# main_board.net
KiCad netlist of a schematic drawn in EAGLE
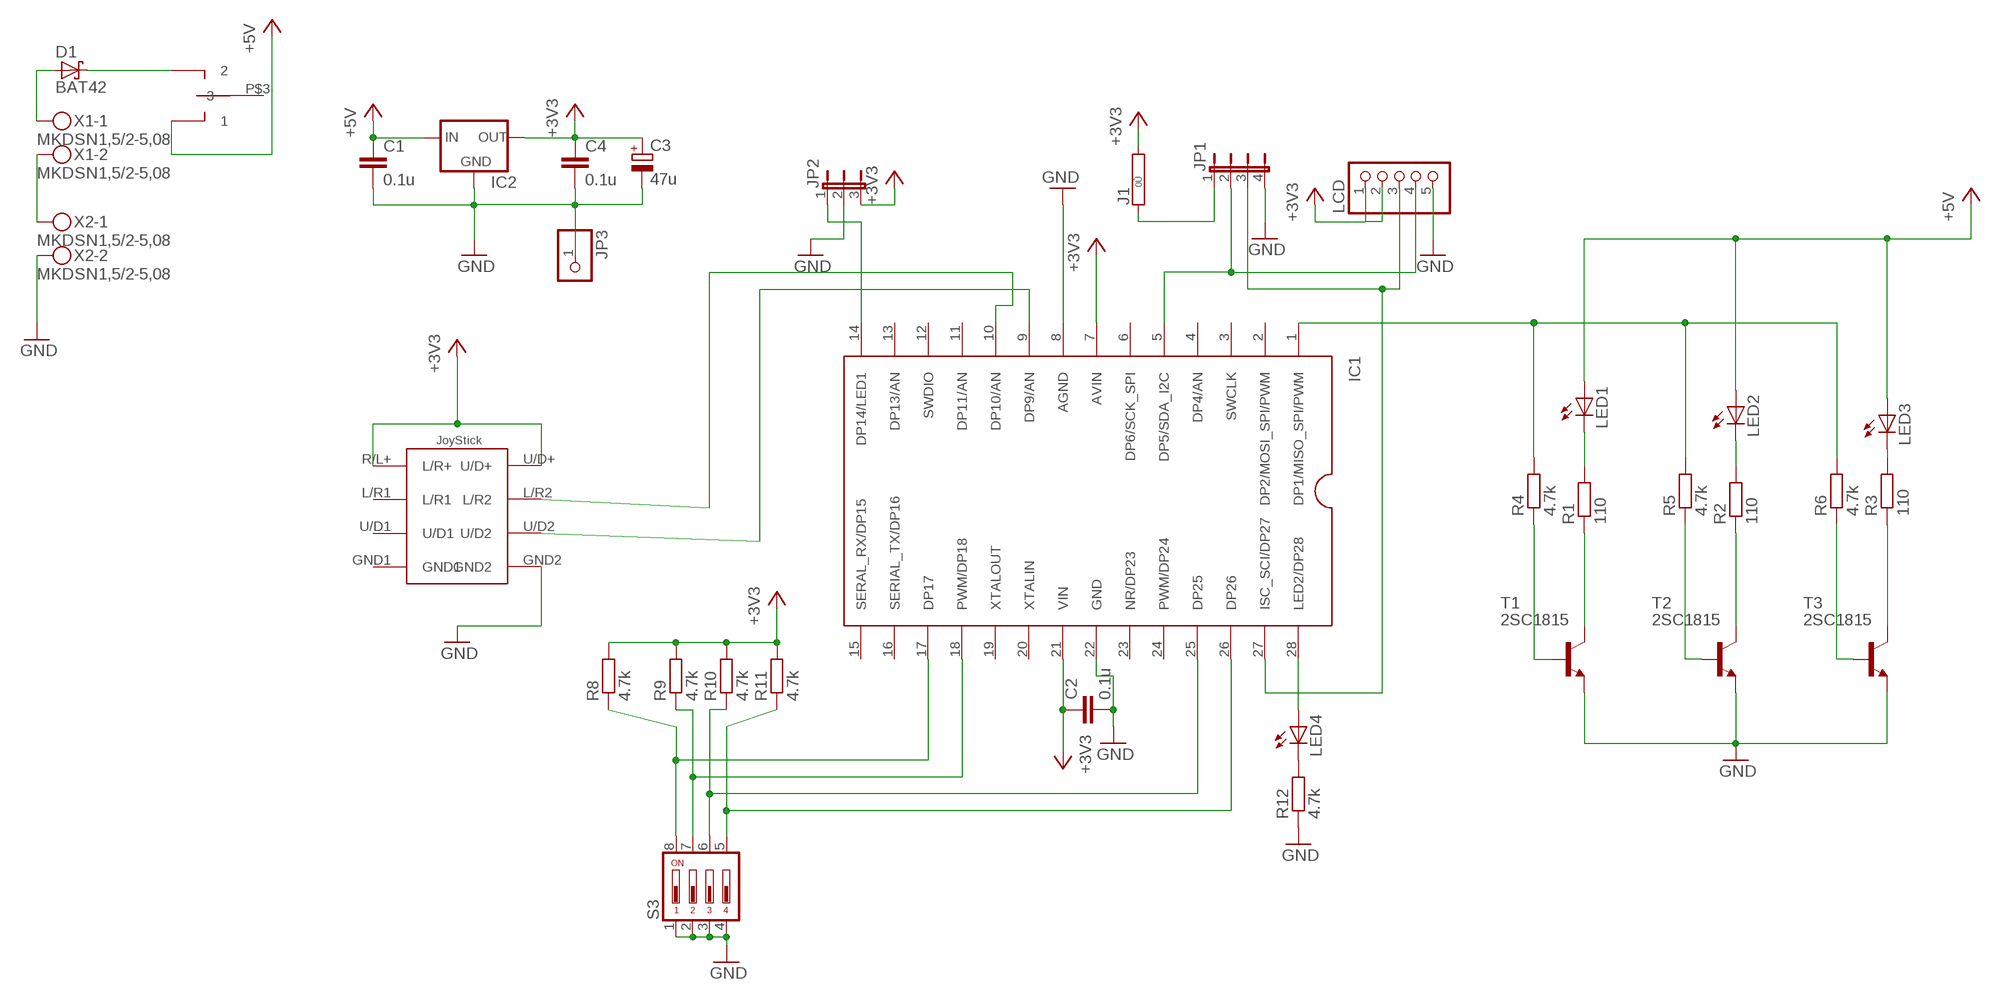
[diagram p0: schematic, sheet 1]

(export (version "E")
  (design (tool "Eeschema 10.0.6"))
  (components
    (comp (ref "C1")
      (value "0.1u")
      (footprint "eagle-import:C025-024X044")
      (libsource (lib "eagle-import") (part "C-EU025-024X044"))
    )
    (comp (ref "C2")
      (value "0.1u")
      (footprint "eagle-import:C025-024X044")
      (libsource (lib "eagle-import") (part "C-EU025-024X044"))
    )
    (comp (ref "C3")
      (value "47u")
      (footprint "eagle-import:E2,5-5")
      (libsource (lib "eagle-import") (part "CPOL-EUE2.5-5"))
    )
    (comp (ref "C4")
      (value "0.1u")
      (footprint "eagle-import:C025-024X044")
      (libsource (lib "eagle-import") (part "C-EU025-024X044"))
    )
    (comp (ref "D1")
      (value "BAT42")
      (footprint "eagle-import:DO35-10")
      (libsource (lib "eagle-import") (part "BAT42"))
    )
    (comp (ref "IC1")
      (value "LPC1114FN28")
      (footprint "eagle-import:DIP28")
      (libsource (lib "eagle-import") (part "LPC1114FN28"))
    )
    (comp (ref "IC2")
      (value "78XXL")
      (footprint "eagle-import:78XXL")
      (libsource (lib "eagle-import") (part "78XXL"))
    )
    (comp (ref "J1")
      (value "0R")
      (footprint "eagle-import:0R_10")
      (libsource (lib "eagle-import") (part "0R"))
    )
    (comp (ref "JP1")
      (value "JP4E")
      (footprint "eagle-import:JP4")
      (libsource (lib "eagle-import") (part "JP4E"))
    )
    (comp (ref "JP2")
      (value "JP2E")
      (footprint "eagle-import:JP2")
      (libsource (lib "eagle-import") (part "JP2E"))
    )
    (comp (ref "JP3")
      (value "PINHD-1X1")
      (footprint "eagle-import:1X01")
      (libsource (lib "eagle-import") (part "PINHD-1X1"))
    )
    (comp (ref "LCD")
      (value "PINHD-1X5")
      (footprint "eagle-import:1X05")
      (libsource (lib "eagle-import") (part "PINHD-1X5"))
    )
    (comp (ref "LED1")
      (value "LED5MM")
      (footprint "eagle-import:LED5MM")
      (libsource (lib "eagle-import") (part "LED5MM"))
    )
    (comp (ref "LED2")
      (value "LED5MM")
      (footprint "eagle-import:LED5MM")
      (libsource (lib "eagle-import") (part "LED5MM"))
    )
    (comp (ref "LED3")
      (value "LED5MM")
      (footprint "eagle-import:LED5MM")
      (libsource (lib "eagle-import") (part "LED5MM"))
    )
    (comp (ref "LED4")
      (value "LED3MM")
      (footprint "eagle-import:LED3MM")
      (libsource (lib "eagle-import") (part "LED3MM"))
    )
    (comp (ref "R1")
      (value "110")
      (footprint "eagle-import:0207_10")
      (libsource (lib "eagle-import") (part "R-EU_0207/10"))
    )
    (comp (ref "R2")
      (value "110")
      (footprint "eagle-import:0207_10")
      (libsource (lib "eagle-import") (part "R-EU_0207/10"))
    )
    (comp (ref "R3")
      (value "110")
      (footprint "eagle-import:0207_10")
      (libsource (lib "eagle-import") (part "R-EU_0207/10"))
    )
    (comp (ref "R4")
      (value "4.7k")
      (footprint "eagle-import:0204_7")
      (libsource (lib "eagle-import") (part "R-EU_0204/7"))
    )
    (comp (ref "R5")
      (value "4.7k")
      (footprint "eagle-import:0204_7")
      (libsource (lib "eagle-import") (part "R-EU_0204/7"))
    )
    (comp (ref "R6")
      (value "4.7k")
      (footprint "eagle-import:0204_7")
      (libsource (lib "eagle-import") (part "R-EU_0204/7"))
    )
    (comp (ref "R8")
      (value "4.7k")
      (footprint "eagle-import:0204_7")
      (libsource (lib "eagle-import") (part "R-EU_0204/7"))
    )
    (comp (ref "R9")
      (value "4.7k")
      (footprint "eagle-import:0204_7")
      (libsource (lib "eagle-import") (part "R-EU_0204/7"))
    )
    (comp (ref "R10")
      (value "4.7k")
      (footprint "eagle-import:0204_7")
      (libsource (lib "eagle-import") (part "R-EU_0204/7"))
    )
    (comp (ref "R11")
      (value "4.7k")
      (footprint "eagle-import:0204_7")
      (libsource (lib "eagle-import") (part "R-EU_0204/7"))
    )
    (comp (ref "R12")
      (value "4.7k")
      (footprint "eagle-import:0204_7")
      (libsource (lib "eagle-import") (part "R-EU_0204/7"))
    )
    (comp (ref "S3")
      (value "DIP04YL")
      (footprint "eagle-import:DIP04YL")
      (libsource (lib "eagle-import") (part "DIP04YL"))
    )
    (comp (ref "T1")
      (value "2SC1815")
      (footprint "eagle-import:TO92-ECB")
      (libsource (lib "eagle-import") (part "2SC1815"))
    )
    (comp (ref "T2")
      (value "2SC1815")
      (footprint "eagle-import:TO92-ECB")
      (libsource (lib "eagle-import") (part "2SC1815"))
    )
    (comp (ref "T3")
      (value "2SC1815")
      (footprint "eagle-import:TO92-ECB")
      (libsource (lib "eagle-import") (part "2SC1815"))
    )
    (comp (ref "U$1")
      (value "ANALOGJOYSTICK")
      (footprint "eagle-import:ANLOGJOYSTICK")
      (libsource (lib "eagle-import") (part "ANALOGJOYSTICK"))
    )
    (comp (ref "U$2")
      (value "TOGGLE-B-12JV")
      (footprint "eagle-import:TOGGLE-B-12JV")
      (libsource (lib "eagle-import") (part "TOGGLE-B-12JV"))
    )
    (comp (ref "X1")
      (value "MKDSN1,5/2-5,08")
      (footprint "eagle-import:MKDSN1,5_2-5,08")
      (libsource (lib "eagle-import") (part "MKDSN1,5/2-5,08"))
    )
    (comp (ref "X2")
      (value "MKDSN1,5/2-5,08")
      (footprint "eagle-import:MKDSN1,5_2-5,08")
      (libsource (lib "eagle-import") (part "MKDSN1,5/2-5,08"))
    )
  )
  (nets
    (net (code "1") (name "+3V3") (class "Default")
      (node (ref "C2") (pin "1") (pinfunction "1_1") (pintype "passive"))
      (node (ref "C3") (pin "+") (pinfunction "+_+") (pintype "passive"))
      (node (ref "C4") (pin "1") (pinfunction "1_1") (pintype "passive"))
      (node (ref "IC1") (pin "21") (pinfunction "VIN_21") (pintype "power_in"))
      (node (ref "IC1") (pin "7") (pinfunction "AVIN_7") (pintype "power_in"))
      (node (ref "IC2") (pin "OUT") (pinfunction "OUT_OUT") (pintype "passive"))
      (node (ref "J1") (pin "2") (pinfunction "2_2") (pintype "passive"))
      (node (ref "JP2") (pin "3") (pinfunction "3_3") (pintype "passive"))
      (node (ref "LCD") (pin "1") (pinfunction "1_1") (pintype "passive"))
      (node (ref "LCD") (pin "2") (pinfunction "2_2") (pintype "passive"))
      (node (ref "R10") (pin "2") (pinfunction "2_2") (pintype "passive"))
      (node (ref "R11") (pin "2") (pinfunction "2_2") (pintype "passive"))
      (node (ref "R8") (pin "2") (pinfunction "2_2") (pintype "passive"))
      (node (ref "R9") (pin "2") (pinfunction "2_2") (pintype "passive"))
      (node (ref "U$1") (pin "R/L+") (pinfunction "L/R+_R/L+") (pintype "bidirectional"))
      (node (ref "U$1") (pin "U/D+") (pinfunction "U/D+_U/D+") (pintype "bidirectional"))
    )
    (net (code "2") (name "+5V") (class "Default")
      (node (ref "C1") (pin "1") (pinfunction "1_1") (pintype "passive"))
      (node (ref "IC2") (pin "IN") (pinfunction "IN_IN") (pintype "input"))
      (node (ref "LED1") (pin "A") (pinfunction "A_A") (pintype "passive"))
      (node (ref "LED2") (pin "A") (pinfunction "A_A") (pintype "passive"))
      (node (ref "LED3") (pin "A") (pinfunction "A_A") (pintype "passive"))
      (node (ref "U$2") (pin "P$1") (pinfunction "1_P$1") (pintype "bidirectional"))
    )
    (net (code "3") (name "GND") (class "Default")
      (node (ref "C1") (pin "2") (pinfunction "2_2") (pintype "passive"))
      (node (ref "C2") (pin "2") (pinfunction "2_2") (pintype "passive"))
      (node (ref "C3") (pin "-") (pinfunction "-_-") (pintype "passive"))
      (node (ref "C4") (pin "2") (pinfunction "2_2") (pintype "passive"))
      (node (ref "IC1") (pin "22") (pinfunction "GND_22") (pintype "power_in"))
      (node (ref "IC1") (pin "8") (pinfunction "AGND_8") (pintype "power_in"))
      (node (ref "IC2") (pin "GND") (pinfunction "GND_GND") (pintype "input"))
      (node (ref "JP1") (pin "4") (pinfunction "4_4") (pintype "passive"))
      (node (ref "JP2") (pin "2") (pinfunction "2_2") (pintype "passive"))
      (node (ref "JP3") (pin "1") (pinfunction "1_1") (pintype "passive"))
      (node (ref "LCD") (pin "5") (pinfunction "5_5") (pintype "passive"))
      (node (ref "R12") (pin "1") (pinfunction "1_1") (pintype "passive"))
      (node (ref "S3") (pin "1") (pinfunction "1_1") (pintype "passive"))
      (node (ref "S3") (pin "2") (pinfunction "2_2") (pintype "passive"))
      (node (ref "S3") (pin "3") (pinfunction "3_3") (pintype "passive"))
      (node (ref "S3") (pin "4") (pinfunction "4_4") (pintype "passive"))
      (node (ref "T1") (pin "E") (pinfunction "E_E") (pintype "passive"))
      (node (ref "T2") (pin "E") (pinfunction "E_E") (pintype "passive"))
      (node (ref "T3") (pin "E") (pinfunction "E_E") (pintype "passive"))
      (node (ref "U$1") (pin "GND2") (pinfunction "GND2_GND2") (pintype "bidirectional"))
      (node (ref "X2") (pin "2") (pinfunction "KL_2") (pintype "passive"))
    )
    (net (code "4") (name "Net-(IC1-DP1{slash}MISO_SPI{slash}PWM)") (class "Default")
      (node (ref "IC1") (pin "1") (pinfunction "DP1/MISO_SPI/PWM_1") (pintype "bidirectional"))
      (node (ref "R4") (pin "2") (pinfunction "2_2") (pintype "passive"))
      (node (ref "R5") (pin "2") (pinfunction "2_2") (pintype "passive"))
      (node (ref "R6") (pin "2") (pinfunction "2_2") (pintype "passive"))
    )
    (net (code "5") (name "Net-(IC1-DP5{slash}SDA_I2C)") (class "Default")
      (node (ref "IC1") (pin "5") (pinfunction "DP5/SDA_I2C_5") (pintype "bidirectional"))
      (node (ref "JP1") (pin "2") (pinfunction "2_2") (pintype "passive"))
      (node (ref "LCD") (pin "4") (pinfunction "4_4") (pintype "passive"))
    )
    (net (code "6") (name "Net-(IC1-DP9{slash}AN)") (class "Default")
      (node (ref "IC1") (pin "9") (pinfunction "DP9/AN_9") (pintype "bidirectional"))
      (node (ref "U$1") (pin "U/D2") (pinfunction "U/D2_U/D2") (pintype "bidirectional"))
    )
    (net (code "7") (name "Net-(IC1-DP10{slash}AN)") (class "Default")
      (node (ref "IC1") (pin "10") (pinfunction "DP10/AN_10") (pintype "bidirectional"))
      (node (ref "U$1") (pin "L/R2") (pinfunction "L/R2_L/R2") (pintype "bidirectional"))
    )
    (net (code "8") (name "Net-(IC1-DP14{slash}LED1)") (class "Default")
      (node (ref "IC1") (pin "14") (pinfunction "DP14/LED1_14") (pintype "bidirectional"))
      (node (ref "JP2") (pin "1") (pinfunction "1_1") (pintype "passive"))
    )
    (net (code "9") (name "Net-(IC1-DP17)") (class "Default")
      (node (ref "IC1") (pin "17") (pinfunction "DP17_17") (pintype "bidirectional"))
      (node (ref "R8") (pin "1") (pinfunction "1_1") (pintype "passive"))
      (node (ref "S3") (pin "8") (pinfunction "8_8") (pintype "passive"))
    )
    (net (code "10") (name "Net-(IC1-DP25)") (class "Default")
      (node (ref "IC1") (pin "25") (pinfunction "DP25_25") (pintype "bidirectional"))
      (node (ref "R10") (pin "1") (pinfunction "1_1") (pintype "passive"))
      (node (ref "S3") (pin "6") (pinfunction "6_6") (pintype "passive"))
    )
    (net (code "11") (name "Net-(IC1-DP26)") (class "Default")
      (node (ref "IC1") (pin "26") (pinfunction "DP26_26") (pintype "bidirectional"))
      (node (ref "R11") (pin "1") (pinfunction "1_1") (pintype "passive"))
      (node (ref "S3") (pin "5") (pinfunction "5_5") (pintype "passive"))
    )
    (net (code "12") (name "Net-(IC1-ISC_SCI{slash}DP27)") (class "Default")
      (node (ref "IC1") (pin "27") (pinfunction "ISC_SCI/DP27_27") (pintype "bidirectional"))
      (node (ref "JP1") (pin "3") (pinfunction "3_3") (pintype "passive"))
      (node (ref "LCD") (pin "3") (pinfunction "3_3") (pintype "passive"))
    )
    (net (code "13") (name "Net-(IC1-LED2{slash}DP28)") (class "Default")
      (node (ref "IC1") (pin "28") (pinfunction "LED2/DP28_28") (pintype "bidirectional"))
      (node (ref "LED4") (pin "A") (pinfunction "A_A") (pintype "passive"))
    )
    (net (code "14") (name "Net-(IC1-PWM{slash}DP18)") (class "Default")
      (node (ref "IC1") (pin "18") (pinfunction "PWM/DP18_18") (pintype "bidirectional"))
      (node (ref "R9") (pin "1") (pinfunction "1_1") (pintype "passive"))
      (node (ref "S3") (pin "7") (pinfunction "7_7") (pintype "passive"))
    )
    (net (code "15") (name "Net-(J1-Pad1)") (class "Default")
      (node (ref "J1") (pin "1") (pinfunction "1_1") (pintype "passive"))
      (node (ref "JP1") (pin "1") (pinfunction "1_1") (pintype "passive"))
    )
    (net (code "16") (name "Net-(LED1-C)") (class "Default")
      (node (ref "LED1") (pin "K") (pinfunction "C_K") (pintype "passive"))
      (node (ref "R1") (pin "2") (pinfunction "2_2") (pintype "passive"))
    )
    (net (code "17") (name "Net-(LED2-C)") (class "Default")
      (node (ref "LED2") (pin "K") (pinfunction "C_K") (pintype "passive"))
      (node (ref "R2") (pin "2") (pinfunction "2_2") (pintype "passive"))
    )
    (net (code "18") (name "Net-(LED3-C)") (class "Default")
      (node (ref "LED3") (pin "K") (pinfunction "C_K") (pintype "passive"))
      (node (ref "R3") (pin "2") (pinfunction "2_2") (pintype "passive"))
    )
    (net (code "19") (name "Net-(LED4-C)") (class "Default")
      (node (ref "LED4") (pin "K") (pinfunction "C_K") (pintype "passive"))
      (node (ref "R12") (pin "2") (pinfunction "2_2") (pintype "passive"))
    )
    (net (code "20") (name "Net-(R1-Pad1)") (class "Default")
      (node (ref "R1") (pin "1") (pinfunction "1_1") (pintype "passive"))
      (node (ref "T1") (pin "C") (pinfunction "C_C") (pintype "passive"))
    )
    (net (code "21") (name "Net-(R2-Pad1)") (class "Default")
      (node (ref "R2") (pin "1") (pinfunction "1_1") (pintype "passive"))
      (node (ref "T2") (pin "C") (pinfunction "C_C") (pintype "passive"))
    )
    (net (code "22") (name "Net-(R3-Pad1)") (class "Default")
      (node (ref "R3") (pin "1") (pinfunction "1_1") (pintype "passive"))
      (node (ref "T3") (pin "C") (pinfunction "C_C") (pintype "passive"))
    )
    (net (code "23") (name "Net-(R4-Pad1)") (class "Default")
      (node (ref "R4") (pin "1") (pinfunction "1_1") (pintype "passive"))
      (node (ref "T1") (pin "B") (pinfunction "B_B") (pintype "passive"))
    )
    (net (code "24") (name "Net-(R5-Pad1)") (class "Default")
      (node (ref "R5") (pin "1") (pinfunction "1_1") (pintype "passive"))
      (node (ref "T2") (pin "B") (pinfunction "B_B") (pintype "passive"))
    )
    (net (code "25") (name "Net-(R6-Pad1)") (class "Default")
      (node (ref "R6") (pin "1") (pinfunction "1_1") (pintype "passive"))
      (node (ref "T3") (pin "B") (pinfunction "B_B") (pintype "passive"))
    )
    (net (code "26") (name "Net-(U$2-2)") (class "Default")
      (node (ref "D1") (pin "C") (pinfunction "C_C") (pintype "passive"))
      (node (ref "U$2") (pin "P$2") (pinfunction "2_P$2") (pintype "bidirectional"))
    )
    (net (code "27") (name "Net-(X1A-KL)") (class "Default")
      (node (ref "D1") (pin "A") (pinfunction "A_A") (pintype "passive"))
      (node (ref "X1") (pin "1") (pinfunction "KL_1") (pintype "passive"))
    )
    (net (code "28") (name "Net-(X1B-KL)") (class "Default")
      (node (ref "X1") (pin "2") (pinfunction "KL_2") (pintype "passive"))
      (node (ref "X2") (pin "1") (pinfunction "KL_1") (pintype "passive"))
    )
    (net (code "29") (name "unconnected-(IC1-DP2{slash}MOSI_SPI{slash}PWM-Pad2)") (class "Default")
      (node (ref "IC1") (pin "2") (pinfunction "DP2/MOSI_SPI/PWM_2") (pintype "bidirectional"))
    )
    (net (code "30") (name "unconnected-(IC1-DP4{slash}AN-Pad4)") (class "Default")
      (node (ref "IC1") (pin "4") (pinfunction "DP4/AN_4") (pintype "bidirectional"))
    )
    (net (code "31") (name "unconnected-(IC1-DP6{slash}SCK_SPI-Pad6)") (class "Default")
      (node (ref "IC1") (pin "6") (pinfunction "DP6/SCK_SPI_6") (pintype "bidirectional"))
    )
    (net (code "32") (name "unconnected-(IC1-DP11{slash}AN-Pad11)") (class "Default")
      (node (ref "IC1") (pin "11") (pinfunction "DP11/AN_11") (pintype "bidirectional"))
    )
    (net (code "33") (name "unconnected-(IC1-DP13{slash}AN-Pad13)") (class "Default")
      (node (ref "IC1") (pin "13") (pinfunction "DP13/AN_13") (pintype "bidirectional"))
    )
    (net (code "34") (name "unconnected-(IC1-NR{slash}DP23-Pad23)") (class "Default")
      (node (ref "IC1") (pin "23") (pinfunction "NR/DP23_23") (pintype "bidirectional"))
    )
    (net (code "35") (name "unconnected-(IC1-PWM{slash}DP24-Pad24)") (class "Default")
      (node (ref "IC1") (pin "24") (pinfunction "PWM/DP24_24") (pintype "bidirectional"))
    )
    (net (code "36") (name "unconnected-(IC1-SERAL_RX{slash}DP15-Pad15)") (class "Default")
      (node (ref "IC1") (pin "15") (pinfunction "SERAL_RX/DP15_15") (pintype "bidirectional"))
    )
    (net (code "37") (name "unconnected-(IC1-SERIAL_TX{slash}DP16-Pad16)") (class "Default")
      (node (ref "IC1") (pin "16") (pinfunction "SERIAL_TX/DP16_16") (pintype "bidirectional"))
    )
    (net (code "38") (name "unconnected-(IC1-SWCLK-Pad3)") (class "Default")
      (node (ref "IC1") (pin "3") (pinfunction "SWCLK_3") (pintype "bidirectional"))
    )
    (net (code "39") (name "unconnected-(IC1-SWDIO-Pad12)") (class "Default")
      (node (ref "IC1") (pin "12") (pinfunction "SWDIO_12") (pintype "bidirectional"))
    )
    (net (code "40") (name "unconnected-(IC1-XTALIN-Pad20)") (class "Default")
      (node (ref "IC1") (pin "20") (pinfunction "XTALIN_20") (pintype "input"))
    )
    (net (code "41") (name "unconnected-(IC1-XTALOUT-Pad19)") (class "Default")
      (node (ref "IC1") (pin "19") (pinfunction "XTALOUT_19") (pintype "output"))
    )
    (net (code "42") (name "unconnected-(U$1-PadGND1)") (class "Default")
      (node (ref "U$1") (pin "GND1") (pinfunction "GND1_GND1") (pintype "bidirectional"))
    )
    (net (code "43") (name "unconnected-(U$1-PadL{slash}R1)") (class "Default")
      (node (ref "U$1") (pin "L/R1") (pinfunction "L/R1_L/R1") (pintype "bidirectional"))
    )
    (net (code "44") (name "unconnected-(U$1-PadU{slash}D1)") (class "Default")
      (node (ref "U$1") (pin "U/D1") (pinfunction "U/D1_U/D1") (pintype "bidirectional"))
    )
    (net (code "45") (name "unconnected-(U$2-3-PadP$3)") (class "Default")
      (node (ref "U$2") (pin "P$3") (pinfunction "3_P$3") (pintype "bidirectional"))
    )
  )
)
